# Barometer.net
KiCad netlist of a schematic drawn in Altium Designer
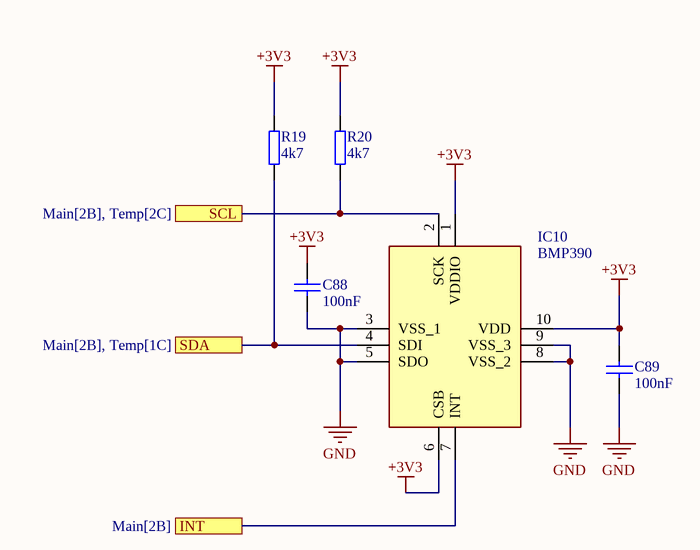
[diagram p0: Barometer.SchDoc]

(export (version "E")
  (design (tool "Eeschema 10.0.6"))
  (components
    (comp (ref "C88")
      (value "100nF")
      (footprint "CAP0402")
      (fields
        (field (name "VOLTAGE") "50V")
        (field (name "MANUFACTURER_PART_NUMBER") "GRM155R71H104ME14D")
        (field (name "Comment") "Cap0402")
      )
      (libsource (lib "capacitorsSMD") (part "Cap0402"))
    )
    (comp (ref "C89")
      (value "100nF")
      (footprint "CAP0402")
      (fields
        (field (name "VOLTAGE") "50V")
        (field (name "MANUFACTURER_PART_NUMBER") "GRM155R71H104ME14D")
        (field (name "Comment") "Cap0402")
      )
      (libsource (lib "capacitorsSMD") (part "Cap0402"))
    )
    (comp (ref "IC10")
      (value "BMP390")
      (footprint "SamacSys:BMP390")
      (description "Integrated Circuit")
      (fields (field (name "MOUSER PART NUMBER") "262-BMP390"))
      (libsource (lib "*") (part "BMP390"))
    )
    (comp (ref "R19")
      (value "4k7")
      (footprint "RES0402")
      (fields (field (name "MANUFACTURER_PART_NUMBER") "RC0402JR-7W4K7L") (field (name "Comment") "Res0402"))
      (libsource (lib "resistorSMD") (part "Res0402"))
    )
    (comp (ref "R20")
      (value "4k7")
      (footprint "RES0402")
      (fields (field (name "MANUFACTURER_PART_NUMBER") "RC0402JR-7W4K7L") (field (name "Comment") "Res0402"))
      (libsource (lib "resistorSMD") (part "Res0402"))
    )
  )
  (nets
    (net (code "1") (name "+3V3") (class "Default")
      (node (ref "C88") (pin "2") (pinfunction "2_2") (pintype "passive"))
      (node (ref "C89") (pin "2") (pinfunction "2_2") (pintype "passive"))
      (node (ref "IC10") (pin "1") (pinfunction "VDDIO_1") (pintype "passive"))
      (node (ref "IC10") (pin "10") (pinfunction "VDD_10") (pintype "passive"))
      (node (ref "IC10") (pin "6") (pinfunction "CSB_6") (pintype "passive"))
      (node (ref "R19") (pin "2") (pinfunction "2_2") (pintype "passive"))
      (node (ref "R20") (pin "2") (pinfunction "2_2") (pintype "passive"))
    )
    (net (code "2") (name "/INT") (class "Default")
      (node (ref "IC10") (pin "7") (pinfunction "INT_7") (pintype "passive"))
    )
    (net (code "3") (name "/SCL") (class "Default")
      (node (ref "IC10") (pin "2") (pinfunction "SCK_2") (pintype "passive"))
      (node (ref "R20") (pin "1") (pinfunction "1_1") (pintype "passive"))
    )
    (net (code "4") (name "/SDA") (class "Default")
      (node (ref "IC10") (pin "4") (pinfunction "SDI_4") (pintype "passive"))
      (node (ref "R19") (pin "1") (pinfunction "1_1") (pintype "passive"))
    )
    (net (code "5") (name "GND") (class "Default")
      (node (ref "C88") (pin "1") (pinfunction "1_1") (pintype "passive"))
      (node (ref "C89") (pin "1") (pinfunction "1_1") (pintype "passive"))
      (node (ref "IC10") (pin "3") (pinfunction "VSS_1_3") (pintype "passive"))
      (node (ref "IC10") (pin "5") (pinfunction "SDO_5") (pintype "passive"))
      (node (ref "IC10") (pin "8") (pinfunction "VSS_2_8") (pintype "passive"))
      (node (ref "IC10") (pin "9") (pinfunction "VSS_3_9") (pintype "passive"))
    )
  )
)
